# tree-v2_2.net
KiCad netlist of a schematic drawn in EAGLE
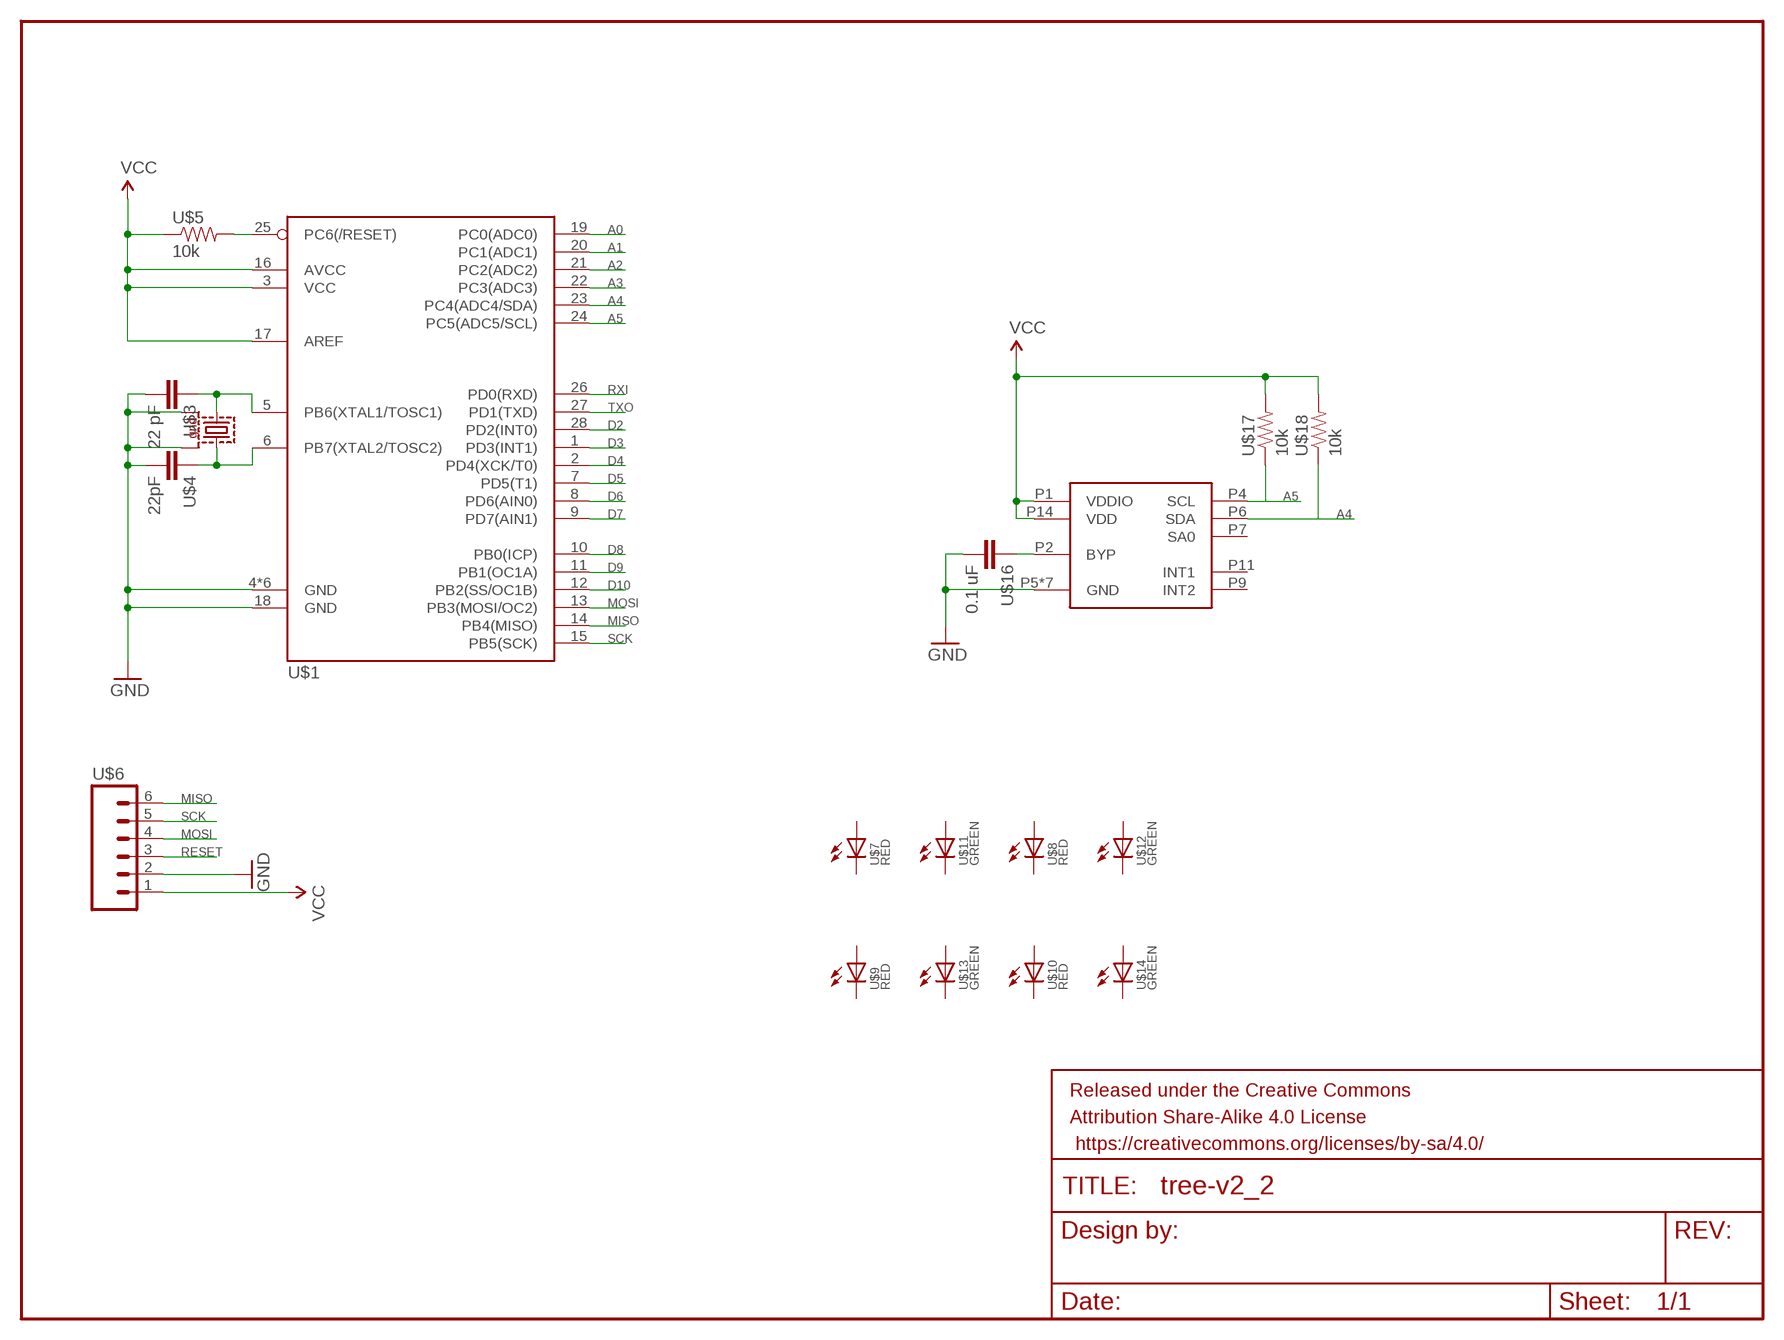
[diagram p0: schematic, sheet 1]

(export (version "E")
  (design (tool "Eeschema 10.0.6"))
  (components
    (comp (ref "FRAME1")
      (value "FRAME-LETTER")
      (footprint "eagle-import:CREATIVE_COMMONS")
      (libsource (lib "eagle-import") (part "FRAME-LETTER"))
    )
    (comp (ref "U$1")
      (value "ATMEGA168-28PINVFQFN-28")
      (footprint "eagle-import:VQFN28")
      (libsource (lib "eagle-import") (part "ATMEGA168-28PINVFQFN-28"))
    )
    (comp (ref "U$2")
      (value "CRYSTAL-SMD-7B-SERIES-TXC")
      (footprint "eagle-import:CRYSTAL-SMD-7B-SERIES-5X3.2MM")
      (fields (field (name "MFG") "TXC") (field (name "MPN") "7B SERIES"))
      (libsource (lib "eagle-import") (part "CRYSTAL-SMD-7B-SERIES-TXC"))
    )
    (comp (ref "U$3")
      (value "22 pF")
      (footprint "eagle-import:CAP-0603")
      (libsource (lib "eagle-import") (part "CAPCAP-0603"))
    )
    (comp (ref "U$4")
      (value "22pF")
      (footprint "eagle-import:CAP-0603")
      (libsource (lib "eagle-import") (part "CAPCAP-0603"))
    )
    (comp (ref "U$5")
      (value "10k")
      (footprint "eagle-import:RES-0603")
      (libsource (lib "eagle-import") (part "RESISTOR0603"))
    )
    (comp (ref "U$6")
      (value "HRD-60.1INCH_NO_SILKSCREEN")
      (footprint "eagle-import:SIP6-SM-0.1IN-NOS.S.")
      (libsource (lib "eagle-import") (part "HRD-60.1INCH_NO_SILKSCREEN"))
    )
    (comp (ref "U$7")
      (value "RED")
      (footprint "eagle-import:LED-1206")
      (libsource (lib "eagle-import") (part "LED1206"))
    )
    (comp (ref "U$8")
      (value "RED")
      (footprint "eagle-import:LED-1206")
      (libsource (lib "eagle-import") (part "LED1206"))
    )
    (comp (ref "U$9")
      (value "RED")
      (footprint "eagle-import:LED-1206")
      (libsource (lib "eagle-import") (part "LED1206"))
    )
    (comp (ref "U$10")
      (value "RED")
      (footprint "eagle-import:LED-1206")
      (libsource (lib "eagle-import") (part "LED1206"))
    )
    (comp (ref "U$11")
      (value "GREEN")
      (footprint "eagle-import:LED-1206")
      (libsource (lib "eagle-import") (part "LED1206"))
    )
    (comp (ref "U$12")
      (value "GREEN")
      (footprint "eagle-import:LED-1206")
      (libsource (lib "eagle-import") (part "LED1206"))
    )
    (comp (ref "U$13")
      (value "GREEN")
      (footprint "eagle-import:LED-1206")
      (libsource (lib "eagle-import") (part "LED1206"))
    )
    (comp (ref "U$14")
      (value "GREEN")
      (footprint "eagle-import:LED-1206")
      (libsource (lib "eagle-import") (part "LED1206"))
    )
    (comp (ref "U$15")
      (value "MMA_8452")
      (footprint "eagle-import:QFN-16-MMA")
      (libsource (lib "eagle-import") (part "MMA_8452"))
    )
    (comp (ref "U$16")
      (value "0.1 uF")
      (footprint "eagle-import:CAP-0603")
      (libsource (lib "eagle-import") (part "CAPCAP-0603"))
    )
    (comp (ref "U$17")
      (value "10k")
      (footprint "eagle-import:RES-0603")
      (libsource (lib "eagle-import") (part "RESISTOR0603"))
    )
    (comp (ref "U$18")
      (value "10k")
      (footprint "eagle-import:RES-0603")
      (libsource (lib "eagle-import") (part "RESISTOR0603"))
    )
  )
  (nets
    (net (code "1") (name "/A0") (class "Default")
      (node (ref "U$1") (pin "19") (pinfunction "PC0(ADC0)_19") (pintype "bidirectional"))
    )
    (net (code "2") (name "/A1") (class "Default")
      (node (ref "U$1") (pin "20") (pinfunction "PC1(ADC1)_20") (pintype "bidirectional"))
    )
    (net (code "3") (name "/A2") (class "Default")
      (node (ref "U$1") (pin "21") (pinfunction "PC2(ADC2)_21") (pintype "bidirectional"))
    )
    (net (code "4") (name "/A3") (class "Default")
      (node (ref "U$1") (pin "22") (pinfunction "PC3(ADC3)_22") (pintype "bidirectional"))
    )
    (net (code "5") (name "/A4") (class "Default")
      (node (ref "U$1") (pin "23") (pinfunction "PC4(ADC4/SDA)_23") (pintype "bidirectional"))
      (node (ref "U$15") (pin "P6") (pinfunction "SDA_P6") (pintype "bidirectional"))
      (node (ref "U$18") (pin "1") (pinfunction "1_1") (pintype "passive"))
    )
    (net (code "6") (name "/A5") (class "Default")
      (node (ref "U$1") (pin "24") (pinfunction "PC5(ADC5/SCL)_24") (pintype "bidirectional"))
      (node (ref "U$15") (pin "P4") (pinfunction "SCL_P4") (pintype "bidirectional"))
      (node (ref "U$17") (pin "1") (pinfunction "1_1") (pintype "passive"))
    )
    (net (code "7") (name "/D2") (class "Default")
      (node (ref "U$1") (pin "28") (pinfunction "PD2(INT0)_28") (pintype "bidirectional"))
    )
    (net (code "8") (name "/D3") (class "Default")
      (node (ref "U$1") (pin "1") (pinfunction "PD3(INT1)_1") (pintype "bidirectional"))
    )
    (net (code "9") (name "/D4") (class "Default")
      (node (ref "U$1") (pin "2") (pinfunction "PD4(XCK/T0)_2") (pintype "bidirectional"))
    )
    (net (code "10") (name "/D5") (class "Default")
      (node (ref "U$1") (pin "7") (pinfunction "PD5(T1)_7") (pintype "bidirectional"))
    )
    (net (code "11") (name "/D6") (class "Default")
      (node (ref "U$1") (pin "8") (pinfunction "PD6(AIN0)_8") (pintype "bidirectional"))
    )
    (net (code "12") (name "/D7") (class "Default")
      (node (ref "U$1") (pin "9") (pinfunction "PD7(AIN1)_9") (pintype "bidirectional"))
    )
    (net (code "13") (name "/D8") (class "Default")
      (node (ref "U$1") (pin "10") (pinfunction "PB0(ICP)_10") (pintype "bidirectional"))
    )
    (net (code "14") (name "/D9") (class "Default")
      (node (ref "U$1") (pin "11") (pinfunction "PB1(OC1A)_11") (pintype "bidirectional"))
    )
    (net (code "15") (name "/D10") (class "Default")
      (node (ref "U$1") (pin "12") (pinfunction "PB2(SS/OC1B)_12") (pintype "bidirectional"))
    )
    (net (code "16") (name "/MISO") (class "Default")
      (node (ref "U$1") (pin "14") (pinfunction "PB4(MISO)_14") (pintype "bidirectional"))
      (node (ref "U$6") (pin "6") (pinfunction "6_6") (pintype "passive"))
    )
    (net (code "17") (name "/MOSI") (class "Default")
      (node (ref "U$1") (pin "13") (pinfunction "PB3(MOSI/OC2)_13") (pintype "bidirectional"))
      (node (ref "U$6") (pin "4") (pinfunction "4_4") (pintype "passive"))
    )
    (net (code "18") (name "/RESET") (class "Default")
      (node (ref "U$1") (pin "25") (pinfunction "PC6(/RESET)_25") (pintype "bidirectional"))
      (node (ref "U$5") (pin "2") (pinfunction "2_2") (pintype "passive"))
      (node (ref "U$6") (pin "3") (pinfunction "3_3") (pintype "passive"))
    )
    (net (code "19") (name "/RXI") (class "Default")
      (node (ref "U$1") (pin "26") (pinfunction "PD0(RXD)_26") (pintype "bidirectional"))
    )
    (net (code "20") (name "/SCK") (class "Default")
      (node (ref "U$1") (pin "15") (pinfunction "PB5(SCK)_15") (pintype "bidirectional"))
      (node (ref "U$6") (pin "5") (pinfunction "5_5") (pintype "passive"))
    )
    (net (code "21") (name "/TXO") (class "Default")
      (node (ref "U$1") (pin "27") (pinfunction "PD1(TXD)_27") (pintype "bidirectional"))
    )
    (net (code "22") (name "GND") (class "Default")
      (node (ref "U$1") (pin "18") (pinfunction "GND_18") (pintype "bidirectional"))
      (node (ref "U$1") (pin "4") (pinfunction "GND_4") (pintype "bidirectional"))
      (node (ref "U$1") (pin "TH") (pinfunction "GND_TH") (pintype "bidirectional"))
      (node (ref "U$1") (pin "TH@1") (pinfunction "GND_TH@1") (pintype "bidirectional"))
      (node (ref "U$1") (pin "TH@2") (pinfunction "GND_TH@2") (pintype "bidirectional"))
      (node (ref "U$1") (pin "TH@3") (pinfunction "GND_TH@3") (pintype "bidirectional"))
      (node (ref "U$1") (pin "TH@4") (pinfunction "GND_TH@4") (pintype "bidirectional"))
      (node (ref "U$15") (pin "P10") (pinfunction "GND_P10") (pintype "power_in"))
      (node (ref "U$15") (pin "P12") (pinfunction "GND_P12") (pintype "power_in"))
      (node (ref "U$15") (pin "P13") (pinfunction "GND_P13") (pintype "power_in"))
      (node (ref "U$15") (pin "P15") (pinfunction "GND_P15") (pintype "power_in"))
      (node (ref "U$15") (pin "P16") (pinfunction "GND_P16") (pintype "power_in"))
      (node (ref "U$15") (pin "P5") (pinfunction "GND_P5") (pintype "power_in"))
      (node (ref "U$15") (pin "P8") (pinfunction "GND_P8") (pintype "power_in"))
      (node (ref "U$16") (pin "2") (pinfunction "2_2") (pintype "passive"))
      (node (ref "U$2") (pin "P$2") (pinfunction "2_P$2") (pintype "passive"))
      (node (ref "U$2") (pin "P$4") (pinfunction "4_P$4") (pintype "passive"))
      (node (ref "U$3") (pin "2") (pinfunction "2_2") (pintype "passive"))
      (node (ref "U$4") (pin "2") (pinfunction "2_2") (pintype "passive"))
      (node (ref "U$6") (pin "2") (pinfunction "2_2") (pintype "passive"))
    )
    (net (code "23") (name "Net-(U$1-PB6(XTAL1{slash}TOSC1))") (class "Default")
      (node (ref "U$1") (pin "5") (pinfunction "PB6(XTAL1/TOSC1)_5") (pintype "bidirectional"))
      (node (ref "U$2") (pin "P$1") (pinfunction "1_P$1") (pintype "passive"))
      (node (ref "U$3") (pin "1") (pinfunction "1_1") (pintype "passive"))
    )
    (net (code "24") (name "Net-(U$1-PB7(XTAL2{slash}TOSC2))") (class "Default")
      (node (ref "U$1") (pin "6") (pinfunction "PB7(XTAL2/TOSC2)_6") (pintype "bidirectional"))
      (node (ref "U$2") (pin "P$3") (pinfunction "3_P$3") (pintype "passive"))
      (node (ref "U$4") (pin "1") (pinfunction "1_1") (pintype "passive"))
    )
    (net (code "25") (name "Net-(U$15-BYP)") (class "Default")
      (node (ref "U$15") (pin "P2") (pinfunction "BYP_P2") (pintype "bidirectional"))
      (node (ref "U$16") (pin "1") (pinfunction "1_1") (pintype "passive"))
    )
    (net (code "26") (name "VCC") (class "Default")
      (node (ref "U$1") (pin "16") (pinfunction "AVCC_16") (pintype "bidirectional"))
      (node (ref "U$1") (pin "17") (pinfunction "AREF_17") (pintype "bidirectional"))
      (node (ref "U$1") (pin "3") (pinfunction "VCC_3") (pintype "bidirectional"))
      (node (ref "U$15") (pin "P1") (pinfunction "VDDIO_P1") (pintype "power_in"))
      (node (ref "U$15") (pin "P14") (pinfunction "VDD_P14") (pintype "power_in"))
      (node (ref "U$17") (pin "2") (pinfunction "2_2") (pintype "passive"))
      (node (ref "U$18") (pin "2") (pinfunction "2_2") (pintype "passive"))
      (node (ref "U$5") (pin "1") (pinfunction "1_1") (pintype "passive"))
      (node (ref "U$6") (pin "1") (pinfunction "1_1") (pintype "passive"))
    )
    (net (code "27") (name "unconnected-(U$7-PadA)") (class "Default")
      (node (ref "U$7") (pin "A") (pinfunction "A_A") (pintype "passive"))
    )
    (net (code "28") (name "unconnected-(U$7-PadC)") (class "Default")
      (node (ref "U$7") (pin "C") (pinfunction "C_C") (pintype "passive"))
    )
    (net (code "29") (name "unconnected-(U$8-PadA)") (class "Default")
      (node (ref "U$8") (pin "A") (pinfunction "A_A") (pintype "passive"))
    )
    (net (code "30") (name "unconnected-(U$8-PadC)") (class "Default")
      (node (ref "U$8") (pin "C") (pinfunction "C_C") (pintype "passive"))
    )
    (net (code "31") (name "unconnected-(U$9-PadA)") (class "Default")
      (node (ref "U$9") (pin "A") (pinfunction "A_A") (pintype "passive"))
    )
    (net (code "32") (name "unconnected-(U$9-PadC)") (class "Default")
      (node (ref "U$9") (pin "C") (pinfunction "C_C") (pintype "passive"))
    )
    (net (code "33") (name "unconnected-(U$10-PadA)") (class "Default")
      (node (ref "U$10") (pin "A") (pinfunction "A_A") (pintype "passive"))
    )
    (net (code "34") (name "unconnected-(U$10-PadC)") (class "Default")
      (node (ref "U$10") (pin "C") (pinfunction "C_C") (pintype "passive"))
    )
    (net (code "35") (name "unconnected-(U$11-PadA)") (class "Default")
      (node (ref "U$11") (pin "A") (pinfunction "A_A") (pintype "passive"))
    )
    (net (code "36") (name "unconnected-(U$11-PadC)") (class "Default")
      (node (ref "U$11") (pin "C") (pinfunction "C_C") (pintype "passive"))
    )
    (net (code "37") (name "unconnected-(U$12-PadA)") (class "Default")
      (node (ref "U$12") (pin "A") (pinfunction "A_A") (pintype "passive"))
    )
    (net (code "38") (name "unconnected-(U$12-PadC)") (class "Default")
      (node (ref "U$12") (pin "C") (pinfunction "C_C") (pintype "passive"))
    )
    (net (code "39") (name "unconnected-(U$13-PadA)") (class "Default")
      (node (ref "U$13") (pin "A") (pinfunction "A_A") (pintype "passive"))
    )
    (net (code "40") (name "unconnected-(U$13-PadC)") (class "Default")
      (node (ref "U$13") (pin "C") (pinfunction "C_C") (pintype "passive"))
    )
    (net (code "41") (name "unconnected-(U$14-PadA)") (class "Default")
      (node (ref "U$14") (pin "A") (pinfunction "A_A") (pintype "passive"))
    )
    (net (code "42") (name "unconnected-(U$14-PadC)") (class "Default")
      (node (ref "U$14") (pin "C") (pinfunction "C_C") (pintype "passive"))
    )
    (net (code "43") (name "unconnected-(U$15-INT1-PadP11)") (class "Default")
      (node (ref "U$15") (pin "P11") (pinfunction "INT1_P11") (pintype "bidirectional"))
    )
    (net (code "44") (name "unconnected-(U$15-INT2-PadP9)") (class "Default")
      (node (ref "U$15") (pin "P9") (pinfunction "INT2_P9") (pintype "bidirectional"))
    )
    (net (code "45") (name "unconnected-(U$15-SA0-PadP7)") (class "Default")
      (node (ref "U$15") (pin "P7") (pinfunction "SA0_P7") (pintype "bidirectional"))
    )
  )
)
